# STM-SIradio.net
KiCad netlist of a schematic drawn in EAGLE
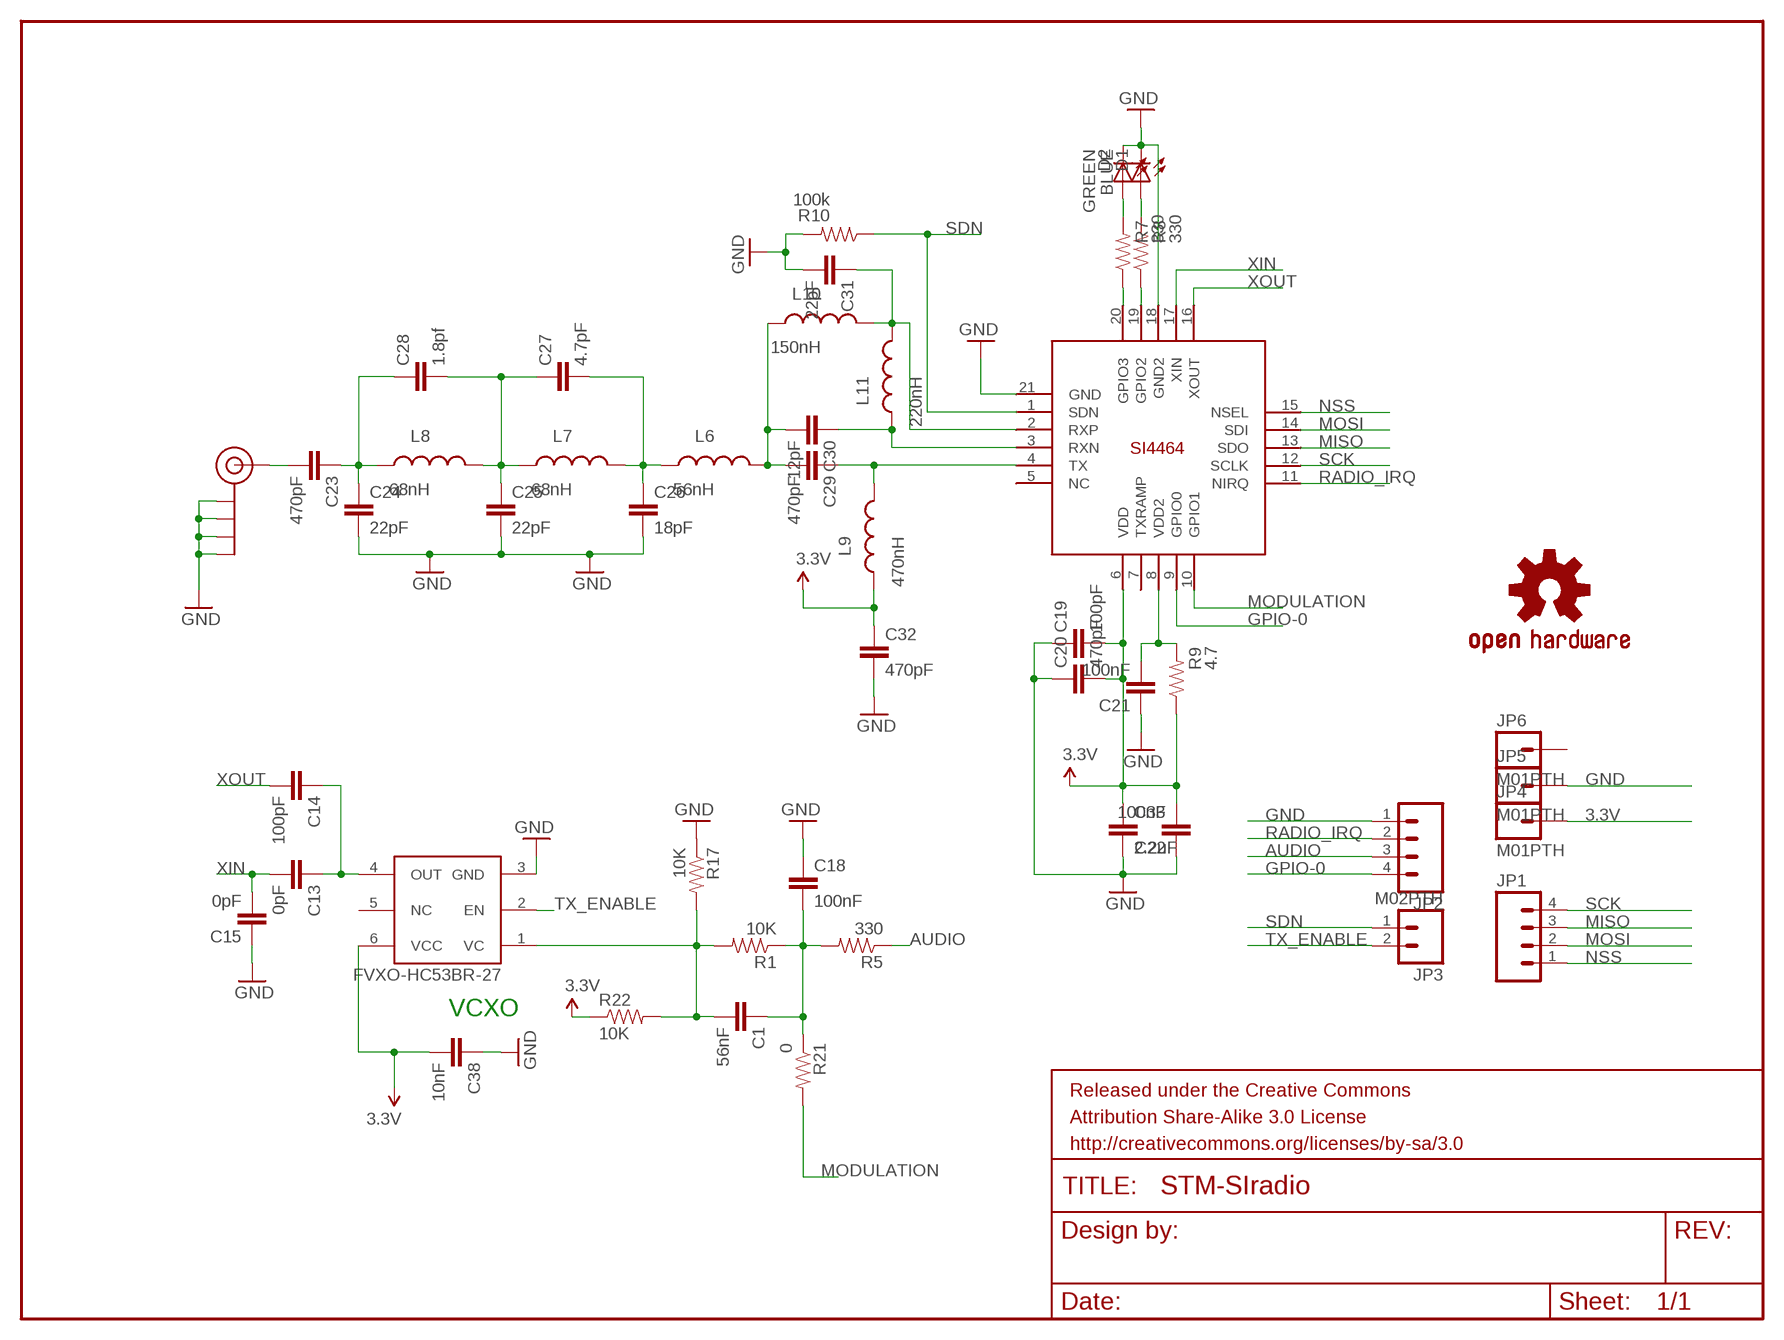
[diagram p0: schematic, sheet 1]

(export (version "E")
  (design (tool "Eeschema 10.0.6"))
  (components
    (comp (ref "C1")
      (value "56nF")
      (footprint "eagle-import:0603-CAP")
      (libsource (lib "eagle-import") (part "CAP0603-CAP"))
    )
    (comp (ref "C13")
      (value "0pF")
      (footprint "eagle-import:0603-CAP")
      (libsource (lib "eagle-import") (part "CAP0603-CAP"))
    )
    (comp (ref "C14")
      (value "100pF")
      (footprint "eagle-import:0603-CAP")
      (libsource (lib "eagle-import") (part "CAP0603-CAP"))
    )
    (comp (ref "C15")
      (value "0pF")
      (footprint "eagle-import:0603-CAP")
      (libsource (lib "eagle-import") (part "CAP0603-CAP"))
    )
    (comp (ref "C18")
      (value "100nF")
      (footprint "eagle-import:0603-CAP")
      (libsource (lib "eagle-import") (part "CAP0603-CAP"))
    )
    (comp (ref "C19")
      (value "100pF")
      (footprint "eagle-import:0603-CAP")
      (libsource (lib "eagle-import") (part "CAP0603-CAP"))
    )
    (comp (ref "C20")
      (value "470pF")
      (footprint "eagle-import:0603-CAP")
      (libsource (lib "eagle-import") (part "CAP0603-CAP"))
    )
    (comp (ref "C21")
      (value "100nF")
      (footprint "eagle-import:0603-CAP")
      (libsource (lib "eagle-import") (part "CAP0603-CAP"))
    )
    (comp (ref "C22")
      (value "100nF")
      (footprint "eagle-import:0603-CAP")
      (libsource (lib "eagle-import") (part "CAP0603-CAP"))
    )
    (comp (ref "C23")
      (value "470pF")
      (footprint "eagle-import:0603-CAP")
      (libsource (lib "eagle-import") (part "CAP0603-CAP"))
    )
    (comp (ref "C24")
      (value "22pF")
      (footprint "eagle-import:0603-CAP")
      (libsource (lib "eagle-import") (part "CAP0603-CAP"))
    )
    (comp (ref "C25")
      (value "22pF")
      (footprint "eagle-import:0603-CAP")
      (libsource (lib "eagle-import") (part "CAP0603-CAP"))
    )
    (comp (ref "C26")
      (value "18pF")
      (footprint "eagle-import:0603-CAP")
      (libsource (lib "eagle-import") (part "CAP0603-CAP"))
    )
    (comp (ref "C27")
      (value "4.7pF")
      (footprint "eagle-import:0603-CAP")
      (libsource (lib "eagle-import") (part "CAP0603-CAP"))
    )
    (comp (ref "C28")
      (value "1.8pf")
      (footprint "eagle-import:0603-CAP")
      (libsource (lib "eagle-import") (part "CAP0603-CAP"))
    )
    (comp (ref "C29")
      (value "470pF")
      (footprint "eagle-import:0603-CAP")
      (libsource (lib "eagle-import") (part "CAP0603-CAP"))
    )
    (comp (ref "C30")
      (value "12pF")
      (footprint "eagle-import:0603-CAP")
      (libsource (lib "eagle-import") (part "CAP0603-CAP"))
    )
    (comp (ref "C31")
      (value "22pF")
      (footprint "eagle-import:0603-CAP")
      (libsource (lib "eagle-import") (part "CAP0603-CAP"))
    )
    (comp (ref "C32")
      (value "470pF")
      (footprint "eagle-import:0603-CAP")
      (libsource (lib "eagle-import") (part "CAP0603-CAP"))
    )
    (comp (ref "C33")
      (value "2.2uF")
      (footprint "eagle-import:1206")
      (libsource (lib "eagle-import") (part "2.2UF-CERCAP-10009"))
    )
    (comp (ref "C38")
      (value "10nF")
      (footprint "eagle-import:0603-CAP")
      (libsource (lib "eagle-import") (part "CAP0603-CAP"))
    )
    (comp (ref "D1")
      (value "BLUE")
      (footprint "eagle-import:LED-0603")
      (libsource (lib "eagle-import") (part "LED-BLUE0603"))
    )
    (comp (ref "D2")
      (value "GREEN")
      (footprint "eagle-import:LED-0603")
      (libsource (lib "eagle-import") (part "LED-GREEN0603"))
    )
    (comp (ref "FRAME1")
      (value "FRAME-LETTER")
      (footprint "eagle-import:CREATIVE_COMMONS")
      (libsource (lib "eagle-import") (part "FRAME-LETTER"))
    )
    (comp (ref "FVXO-HC53BR-27")
      (value "VCXO-SMDSMD3X")
      (footprint "eagle-import:VCXO-SMD-5X3.2")
      (libsource (lib "eagle-import") (part "VCXO-SMDSMD3X"))
    )
    (comp (ref "J$2")
      (value "SMA_EDGE")
      (footprint "eagle-import:SMA-EDGE")
      (libsource (lib "eagle-import") (part "SMA_EDGE"))
    )
    (comp (ref "JP1")
      (value "M04PTH")
      (footprint "eagle-import:1X04")
      (libsource (lib "eagle-import") (part "M04PTH"))
    )
    (comp (ref "JP2")
      (value "M04PTH")
      (footprint "eagle-import:1X04")
      (libsource (lib "eagle-import") (part "M04PTH"))
    )
    (comp (ref "JP3")
      (value "M02PTH")
      (footprint "eagle-import:1X02")
      (libsource (lib "eagle-import") (part "M02PTH"))
    )
    (comp (ref "JP4")
      (value "M01PTH")
      (footprint "eagle-import:1X01")
      (libsource (lib "eagle-import") (part "M01PTH"))
    )
    (comp (ref "JP5")
      (value "M01PTH")
      (footprint "eagle-import:1X01")
      (libsource (lib "eagle-import") (part "M01PTH"))
    )
    (comp (ref "JP6")
      (value "M01PTH")
      (footprint "eagle-import:1X01")
      (libsource (lib "eagle-import") (part "M01PTH"))
    )
    (comp (ref "L6")
      (value "56nH")
      (footprint "eagle-import:0603")
      (libsource (lib "eagle-import") (part "INDUCTOR0603"))
    )
    (comp (ref "L7")
      (value "68nH")
      (footprint "eagle-import:0603")
      (libsource (lib "eagle-import") (part "INDUCTOR0603"))
    )
    (comp (ref "L8")
      (value "68nH")
      (footprint "eagle-import:0603")
      (libsource (lib "eagle-import") (part "INDUCTOR0603"))
    )
    (comp (ref "L9")
      (value "470nH")
      (footprint "eagle-import:0603")
      (libsource (lib "eagle-import") (part "INDUCTOR0603"))
    )
    (comp (ref "L10")
      (value "150nH")
      (footprint "eagle-import:0603")
      (libsource (lib "eagle-import") (part "INDUCTOR0603"))
    )
    (comp (ref "L11")
      (value "220nH")
      (footprint "eagle-import:0603")
      (libsource (lib "eagle-import") (part "INDUCTOR0603"))
    )
    (comp (ref "LOGO1")
      (value "OSHW-LOGOL")
      (footprint "eagle-import:OSHW-LOGO-L")
      (libsource (lib "eagle-import") (part "OSHW-LOGOL"))
    )
    (comp (ref "R1")
      (value "10K")
      (footprint "eagle-import:0603-RES")
      (libsource (lib "eagle-import") (part "RESISTOR0603"))
    )
    (comp (ref "R5")
      (value "330")
      (footprint "eagle-import:0603-RES")
      (libsource (lib "eagle-import") (part "RESISTOR0603"))
    )
    (comp (ref "R7")
      (value "330")
      (footprint "eagle-import:0603-RES")
      (libsource (lib "eagle-import") (part "RESISTOR0603-RES"))
    )
    (comp (ref "R8")
      (value "330")
      (footprint "eagle-import:0603-RES")
      (libsource (lib "eagle-import") (part "RESISTOR0603-RES"))
    )
    (comp (ref "R9")
      (value "4.7")
      (footprint "eagle-import:0603-RES")
      (libsource (lib "eagle-import") (part "RESISTOR0603-RES"))
    )
    (comp (ref "R10")
      (value "100k")
      (footprint "eagle-import:0603-RES")
      (libsource (lib "eagle-import") (part "RESISTOR0603-RES"))
    )
    (comp (ref "R17")
      (value "10K")
      (footprint "eagle-import:0603-RES")
      (libsource (lib "eagle-import") (part "RESISTOR0603"))
    )
    (comp (ref "R21")
      (value "0")
      (footprint "eagle-import:0603-RES")
      (libsource (lib "eagle-import") (part "RESISTOR0603"))
    )
    (comp (ref "R22")
      (value "10K")
      (footprint "eagle-import:0603-RES")
      (libsource (lib "eagle-import") (part "RESISTOR0603"))
    )
    (comp (ref "U$3")
      (value "SI4464")
      (footprint "eagle-import:QFN20+GNDPAD")
      (libsource (lib "eagle-import") (part "SI4464"))
    )
  )
  (nets
    (net (code "1") (name "/AUDIO") (class "Default")
      (node (ref "JP2") (pin "3") (pinfunction "3_3") (pintype "passive"))
      (node (ref "R5") (pin "1") (pinfunction "1_1") (pintype "passive"))
    )
    (net (code "2") (name "/GPIO-0") (class "Default")
      (node (ref "JP2") (pin "4") (pinfunction "4_4") (pintype "passive"))
      (node (ref "U$3") (pin "9") (pinfunction "GPIO0_9") (pintype "bidirectional"))
    )
    (net (code "3") (name "/MISO") (class "Default")
      (node (ref "JP1") (pin "3") (pinfunction "3_3") (pintype "passive"))
      (node (ref "U$3") (pin "13") (pinfunction "SDO_13") (pintype "bidirectional"))
    )
    (net (code "4") (name "/MODULATION") (class "Default")
      (node (ref "R21") (pin "2") (pinfunction "2_2") (pintype "passive"))
      (node (ref "U$3") (pin "10") (pinfunction "GPIO1_10") (pintype "bidirectional"))
    )
    (net (code "5") (name "/MOSI") (class "Default")
      (node (ref "JP1") (pin "2") (pinfunction "2_2") (pintype "passive"))
      (node (ref "U$3") (pin "14") (pinfunction "SDI_14") (pintype "bidirectional"))
    )
    (net (code "6") (name "/NSS") (class "Default")
      (node (ref "JP1") (pin "1") (pinfunction "1_1") (pintype "passive"))
      (node (ref "U$3") (pin "15") (pinfunction "NSEL_15") (pintype "bidirectional"))
    )
    (net (code "7") (name "/RADIO_IRQ") (class "Default")
      (node (ref "JP2") (pin "2") (pinfunction "2_2") (pintype "passive"))
      (node (ref "U$3") (pin "11") (pinfunction "NIRQ_11") (pintype "bidirectional"))
    )
    (net (code "8") (name "/SCK") (class "Default")
      (node (ref "JP1") (pin "4") (pinfunction "4_4") (pintype "passive"))
      (node (ref "U$3") (pin "12") (pinfunction "SCLK_12") (pintype "bidirectional"))
    )
    (net (code "9") (name "/SDN") (class "Default")
      (node (ref "JP3") (pin "1") (pinfunction "1_1") (pintype "passive"))
      (node (ref "R10") (pin "1") (pinfunction "1_1") (pintype "passive"))
      (node (ref "U$3") (pin "1") (pinfunction "SDN_1") (pintype "bidirectional"))
    )
    (net (code "10") (name "/TX_ENABLE") (class "Default")
      (node (ref "FVXO-HC53BR-27") (pin "2") (pinfunction "EN_2") (pintype "bidirectional"))
      (node (ref "JP3") (pin "2") (pinfunction "2_2") (pintype "passive"))
    )
    (net (code "11") (name "/XIN") (class "Default")
      (node (ref "C13") (pin "2") (pinfunction "2_2") (pintype "passive"))
      (node (ref "C15") (pin "2") (pinfunction "2_2") (pintype "passive"))
      (node (ref "U$3") (pin "17") (pinfunction "XIN_17") (pintype "bidirectional"))
    )
    (net (code "12") (name "/XOUT") (class "Default")
      (node (ref "C14") (pin "2") (pinfunction "2_2") (pintype "passive"))
      (node (ref "U$3") (pin "16") (pinfunction "XOUT_16") (pintype "bidirectional"))
    )
    (net (code "13") (name "3.3V") (class "Default")
      (node (ref "C19") (pin "2") (pinfunction "2_2") (pintype "passive"))
      (node (ref "C20") (pin "2") (pinfunction "2_2") (pintype "passive"))
      (node (ref "C22") (pin "2") (pinfunction "2_2") (pintype "passive"))
      (node (ref "C32") (pin "1") (pinfunction "1_1") (pintype "passive"))
      (node (ref "C33") (pin "1") (pinfunction "1_1") (pintype "passive"))
      (node (ref "C38") (pin "2") (pinfunction "2_2") (pintype "passive"))
      (node (ref "FVXO-HC53BR-27") (pin "6") (pinfunction "VCC_6") (pintype "bidirectional"))
      (node (ref "JP4") (pin "1") (pinfunction "1_1") (pintype "passive"))
      (node (ref "L9") (pin "1") (pinfunction "1_1") (pintype "passive"))
      (node (ref "R22") (pin "1") (pinfunction "1_1") (pintype "passive"))
      (node (ref "R9") (pin "1") (pinfunction "1_1") (pintype "passive"))
      (node (ref "U$3") (pin "6") (pinfunction "VDD_6") (pintype "bidirectional"))
    )
    (net (code "14") (name "GND") (class "Default")
      (node (ref "C15") (pin "1") (pinfunction "1_1") (pintype "passive"))
      (node (ref "C18") (pin "1") (pinfunction "1_1") (pintype "passive"))
      (node (ref "C19") (pin "1") (pinfunction "1_1") (pintype "passive"))
      (node (ref "C20") (pin "1") (pinfunction "1_1") (pintype "passive"))
      (node (ref "C21") (pin "1") (pinfunction "1_1") (pintype "passive"))
      (node (ref "C22") (pin "1") (pinfunction "1_1") (pintype "passive"))
      (node (ref "C24") (pin "2") (pinfunction "2_2") (pintype "passive"))
      (node (ref "C25") (pin "2") (pinfunction "2_2") (pintype "passive"))
      (node (ref "C26") (pin "2") (pinfunction "2_2") (pintype "passive"))
      (node (ref "C31") (pin "2") (pinfunction "2_2") (pintype "passive"))
      (node (ref "C32") (pin "2") (pinfunction "2_2") (pintype "passive"))
      (node (ref "C33") (pin "2") (pinfunction "2_2") (pintype "passive"))
      (node (ref "C38") (pin "1") (pinfunction "1_1") (pintype "passive"))
      (node (ref "D1") (pin "C") (pinfunction "C_C") (pintype "passive"))
      (node (ref "D2") (pin "C") (pinfunction "C_C") (pintype "passive"))
      (node (ref "FVXO-HC53BR-27") (pin "3") (pinfunction "GND_3") (pintype "bidirectional"))
      (node (ref "J$2") (pin "GND@0") (pinfunction "GND_GND@0") (pintype "bidirectional"))
      (node (ref "J$2") (pin "GND@1") (pinfunction "GND_GND@1") (pintype "bidirectional"))
      (node (ref "J$2") (pin "GND@2") (pinfunction "GND_GND@2") (pintype "bidirectional"))
      (node (ref "J$2") (pin "GND@3") (pinfunction "GND_GND@3") (pintype "bidirectional"))
      (node (ref "JP2") (pin "1") (pinfunction "1_1") (pintype "passive"))
      (node (ref "JP5") (pin "1") (pinfunction "1_1") (pintype "passive"))
      (node (ref "R10") (pin "2") (pinfunction "2_2") (pintype "passive"))
      (node (ref "R17") (pin "1") (pinfunction "1_1") (pintype "passive"))
      (node (ref "U$3") (pin "18") (pinfunction "GND2_18") (pintype "bidirectional"))
      (node (ref "U$3") (pin "21") (pinfunction "GND_21") (pintype "bidirectional"))
    )
    (net (code "15") (name "Net-(C1-Pad1)") (class "Default")
      (node (ref "C1") (pin "1") (pinfunction "1_1") (pintype "passive"))
      (node (ref "C18") (pin "2") (pinfunction "2_2") (pintype "passive"))
      (node (ref "R1") (pin "1") (pinfunction "1_1") (pintype "passive"))
      (node (ref "R21") (pin "1") (pinfunction "1_1") (pintype "passive"))
      (node (ref "R5") (pin "2") (pinfunction "2_2") (pintype "passive"))
    )
    (net (code "16") (name "Net-(C23-Pad1)") (class "Default")
      (node (ref "C23") (pin "1") (pinfunction "1_1") (pintype "passive"))
      (node (ref "C24") (pin "1") (pinfunction "1_1") (pintype "passive"))
      (node (ref "C28") (pin "1") (pinfunction "1_1") (pintype "passive"))
      (node (ref "L8") (pin "1") (pinfunction "1_1") (pintype "passive"))
    )
    (net (code "17") (name "Net-(C25-Pad1)") (class "Default")
      (node (ref "C25") (pin "1") (pinfunction "1_1") (pintype "passive"))
      (node (ref "C27") (pin "1") (pinfunction "1_1") (pintype "passive"))
      (node (ref "C28") (pin "2") (pinfunction "2_2") (pintype "passive"))
      (node (ref "L7") (pin "1") (pinfunction "1_1") (pintype "passive"))
      (node (ref "L8") (pin "2") (pinfunction "2_2") (pintype "passive"))
    )
    (net (code "18") (name "Net-(C26-Pad1)") (class "Default")
      (node (ref "C26") (pin "1") (pinfunction "1_1") (pintype "passive"))
      (node (ref "C27") (pin "2") (pinfunction "2_2") (pintype "passive"))
      (node (ref "L6") (pin "1") (pinfunction "1_1") (pintype "passive"))
      (node (ref "L7") (pin "2") (pinfunction "2_2") (pintype "passive"))
    )
    (net (code "19") (name "Net-(C29-Pad2)") (class "Default")
      (node (ref "C29") (pin "2") (pinfunction "2_2") (pintype "passive"))
      (node (ref "C30") (pin "2") (pinfunction "2_2") (pintype "passive"))
      (node (ref "L10") (pin "1") (pinfunction "1_1") (pintype "passive"))
      (node (ref "L6") (pin "2") (pinfunction "2_2") (pintype "passive"))
    )
    (net (code "20") (name "Net-(D1-PadA)") (class "Default")
      (node (ref "D1") (pin "A") (pinfunction "A_A") (pintype "passive"))
      (node (ref "R8") (pin "2") (pinfunction "2_2") (pintype "passive"))
    )
    (net (code "21") (name "Net-(D2-PadA)") (class "Default")
      (node (ref "D2") (pin "A") (pinfunction "A_A") (pintype "passive"))
      (node (ref "R7") (pin "2") (pinfunction "2_2") (pintype "passive"))
    )
    (net (code "22") (name "Net-(FVXO-HC53BR-27-OUT)") (class "Default")
      (node (ref "C13") (pin "1") (pinfunction "1_1") (pintype "passive"))
      (node (ref "C14") (pin "1") (pinfunction "1_1") (pintype "passive"))
      (node (ref "FVXO-HC53BR-27") (pin "4") (pinfunction "OUT_4") (pintype "bidirectional"))
    )
    (net (code "23") (name "Net-(FVXO-HC53BR-27-VC)") (class "Default")
      (node (ref "C1") (pin "2") (pinfunction "2_2") (pintype "passive"))
      (node (ref "FVXO-HC53BR-27") (pin "1") (pinfunction "VC_1") (pintype "bidirectional"))
      (node (ref "R1") (pin "2") (pinfunction "2_2") (pintype "passive"))
      (node (ref "R17") (pin "2") (pinfunction "2_2") (pintype "passive"))
      (node (ref "R22") (pin "2") (pinfunction "2_2") (pintype "passive"))
    )
    (net (code "24") (name "Net-(J$2-SIGNAL)") (class "Default")
      (node (ref "C23") (pin "2") (pinfunction "2_2") (pintype "passive"))
      (node (ref "J$2") (pin "SIG") (pinfunction "SIGNAL_SIG") (pintype "bidirectional"))
    )
    (net (code "25") (name "Net-(U$3-GPIO2)") (class "Default")
      (node (ref "R8") (pin "1") (pinfunction "1_1") (pintype "passive"))
      (node (ref "U$3") (pin "19") (pinfunction "GPIO2_19") (pintype "bidirectional"))
    )
    (net (code "26") (name "Net-(U$3-GPIO3)") (class "Default")
      (node (ref "R7") (pin "1") (pinfunction "1_1") (pintype "passive"))
      (node (ref "U$3") (pin "20") (pinfunction "GPIO3_20") (pintype "bidirectional"))
    )
    (net (code "27") (name "Net-(U$3-RXN)") (class "Default")
      (node (ref "C30") (pin "1") (pinfunction "1_1") (pintype "passive"))
      (node (ref "L11") (pin "1") (pinfunction "1_1") (pintype "passive"))
      (node (ref "U$3") (pin "3") (pinfunction "RXN_3") (pintype "bidirectional"))
    )
    (net (code "28") (name "Net-(U$3-RXP)") (class "Default")
      (node (ref "C31") (pin "1") (pinfunction "1_1") (pintype "passive"))
      (node (ref "L10") (pin "2") (pinfunction "2_2") (pintype "passive"))
      (node (ref "L11") (pin "2") (pinfunction "2_2") (pintype "passive"))
      (node (ref "U$3") (pin "2") (pinfunction "RXP_2") (pintype "bidirectional"))
    )
    (net (code "29") (name "Net-(U$3-TX)") (class "Default")
      (node (ref "C29") (pin "1") (pinfunction "1_1") (pintype "passive"))
      (node (ref "L9") (pin "2") (pinfunction "2_2") (pintype "passive"))
      (node (ref "U$3") (pin "4") (pinfunction "TX_4") (pintype "bidirectional"))
    )
    (net (code "30") (name "Net-(U$3-VDD2)") (class "Default")
      (node (ref "C21") (pin "2") (pinfunction "2_2") (pintype "passive"))
      (node (ref "R9") (pin "2") (pinfunction "2_2") (pintype "passive"))
      (node (ref "U$3") (pin "8") (pinfunction "VDD2_8") (pintype "bidirectional"))
    )
    (net (code "31") (name "unconnected-(FVXO-HC53BR-27-NC-Pad5)") (class "Default")
      (node (ref "FVXO-HC53BR-27") (pin "5") (pinfunction "NC_5") (pintype "bidirectional"))
    )
    (net (code "32") (name "unconnected-(JP6-Pad1)") (class "Default")
      (node (ref "JP6") (pin "1") (pinfunction "1_1") (pintype "passive"))
    )
    (net (code "33") (name "unconnected-(U$3-NC -Pad5)") (class "Default")
      (node (ref "U$3") (pin "5") (pinfunction "NC _5") (pintype "bidirectional"))
    )
    (net (code "34") (name "unconnected-(U$3-TXRAMP-Pad7)") (class "Default")
      (node (ref "U$3") (pin "7") (pinfunction "TXRAMP_7") (pintype "bidirectional"))
    )
  )
)
